# ADC.net
KiCad netlist of a schematic drawn in Altium Designer
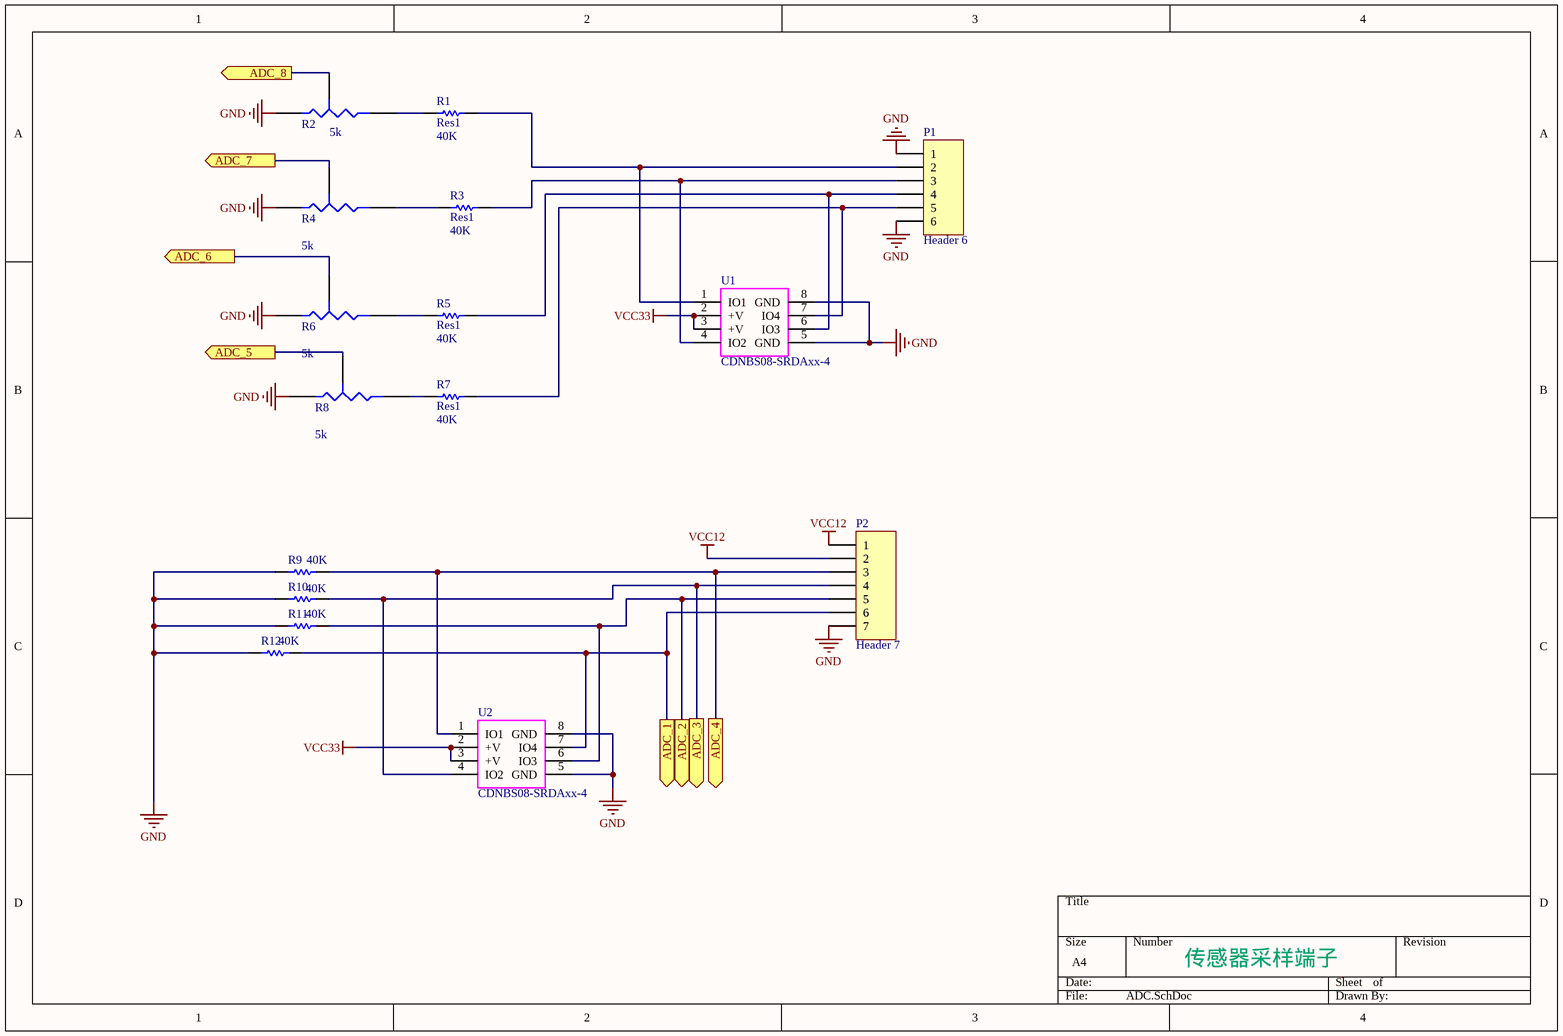
[diagram p0: ADC.SchDoc]

(export (version "E")
  (design (tool "Eeschema 10.0.6"))
  (components
    (comp (ref "P1")
      (value "Header 6")
      (footprint "3.81-6P")
      (description "Header, 6-Pin")
      (fields (field (name "PUBLISHER") "Altium Limited"))
      (libsource (lib "Miscellaneous Connectors") (part "Header 6"))
    )
    (comp (ref "P2")
      (value "Header 7")
      (footprint "3.81-7P")
      (description "Header, 7-Pin")
      (fields (field (name "PUBLISHER") "Altium Limited"))
      (libsource (lib "Miscellaneous Connectors") (part "Header 7"))
    )
    (comp (ref "R1")
      (value "Res1")
      (footprint "AXIAL-0.1")
      (description "Resistor")
      (fields (field (name "ALTIUM_VALUE") "40K") (field (name "PUBLISHER") "Altium Limited"))
      (libsource (lib "Miscellaneous Devices") (part "Res1"))
    )
    (comp (ref "R2")
      (value "5k")
      (footprint "RES-RV3296W")
      (description "Tapped Resistor")
      (fields (field (name "Comment") "Res Tap") (field (name "PUBLISHER") "Altium Limited"))
      (libsource (lib "Miscellaneous Devices") (part "Res Tap"))
    )
    (comp (ref "R3")
      (value "Res1")
      (footprint "AXIAL-0.1")
      (description "Resistor")
      (fields (field (name "ALTIUM_VALUE") "40K") (field (name "PUBLISHER") "Altium Limited"))
      (libsource (lib "Miscellaneous Devices") (part "Res1"))
    )
    (comp (ref "R4")
      (value "5k")
      (footprint "RES-RV3296W")
      (description "Tapped Resistor")
      (fields (field (name "Comment") "Res Tap") (field (name "PUBLISHER") "Altium Limited"))
      (libsource (lib "Miscellaneous Devices") (part "Res Tap"))
    )
    (comp (ref "R5")
      (value "Res1")
      (footprint "AXIAL-0.1")
      (description "Resistor")
      (fields (field (name "ALTIUM_VALUE") "40K") (field (name "PUBLISHER") "Altium Limited"))
      (libsource (lib "Miscellaneous Devices") (part "Res1"))
    )
    (comp (ref "R6")
      (value "5k")
      (footprint "RES-RV3296W")
      (description "Tapped Resistor")
      (fields (field (name "Comment") "Res Tap") (field (name "PUBLISHER") "Altium Limited"))
      (libsource (lib "Miscellaneous Devices") (part "Res Tap"))
    )
    (comp (ref "R7")
      (value "Res1")
      (footprint "AXIAL-0.1")
      (description "Resistor")
      (fields (field (name "ALTIUM_VALUE") "40K") (field (name "PUBLISHER") "Altium Limited"))
      (libsource (lib "Miscellaneous Devices") (part "Res1"))
    )
    (comp (ref "R8")
      (value "5k")
      (footprint "RES-RV3296W")
      (description "Tapped Resistor")
      (fields (field (name "Comment") "Res Tap") (field (name "PUBLISHER") "Altium Limited"))
      (libsource (lib "Miscellaneous Devices") (part "Res Tap"))
    )
    (comp (ref "R9")
      (value "40K")
      (footprint "AXIAL-0.2")
      (description "Resistor")
      (fields (field (name "Comment") "Res1") (field (name "PUBLISHER") "Altium Limited"))
      (libsource (lib "Miscellaneous Devices") (part "Res1"))
    )
    (comp (ref "R10")
      (value "40K")
      (footprint "AXIAL-0.2")
      (description "Resistor")
      (fields (field (name "Comment") "Res1") (field (name "PUBLISHER") "Altium Limited"))
      (libsource (lib "Miscellaneous Devices") (part "Res1"))
    )
    (comp (ref "R11")
      (value "40K")
      (footprint "AXIAL-0.2")
      (description "Resistor")
      (fields (field (name "Comment") "Res1") (field (name "PUBLISHER") "Altium Limited"))
      (libsource (lib "Miscellaneous Devices") (part "Res1"))
    )
    (comp (ref "R12")
      (value "40K")
      (footprint "AXIAL-0.2")
      (description "Resistor")
      (fields (field (name "Comment") "Res1") (field (name "PUBLISHER") "Altium Limited"))
      (libsource (lib "Miscellaneous Devices") (part "Res1"))
    )
    (comp (ref "U1")
      (value "CDNBS08-SRDAxx-4")
      (footprint "CDNBS08-SRDAxx-4")
      (libsource (lib "Active_crystal") (part "CDNBS08-SRDAxx-4"))
    )
    (comp (ref "U2")
      (value "CDNBS08-SRDAxx-4")
      (footprint "CDNBS08-SRDAxx-4")
      (libsource (lib "Active_crystal") (part "CDNBS08-SRDAxx-4"))
    )
  )
  (nets
    (net (code "1") (name "/ADC_1") (class "Default")
      (node (ref "P2") (pin "6") (pinfunction "6_6") (pintype "passive"))
      (node (ref "R12") (pin "2") (pinfunction "2_2") (pintype "passive"))
      (node (ref "U2") (pin "7") (pinfunction "IO4_7") (pintype "passive"))
    )
    (net (code "2") (name "/ADC_2") (class "Default")
      (node (ref "P2") (pin "5") (pinfunction "5_5") (pintype "passive"))
      (node (ref "R11") (pin "2") (pinfunction "2_2") (pintype "passive"))
      (node (ref "U2") (pin "6") (pinfunction "IO3_6") (pintype "passive"))
    )
    (net (code "3") (name "/ADC_3") (class "Default")
      (node (ref "P2") (pin "4") (pinfunction "4_4") (pintype "passive"))
      (node (ref "R10") (pin "2") (pinfunction "2_2") (pintype "passive"))
      (node (ref "U2") (pin "4") (pinfunction "IO2_4") (pintype "passive"))
    )
    (net (code "4") (name "/ADC_4") (class "Default")
      (node (ref "P2") (pin "3") (pinfunction "3_3") (pintype "passive"))
      (node (ref "R9") (pin "2") (pinfunction "2_2") (pintype "passive"))
      (node (ref "U2") (pin "1") (pinfunction "IO1_1") (pintype "passive"))
    )
    (net (code "5") (name "/ADC_5") (class "Default")
      (node (ref "R8") (pin "3") (pinfunction "TAP_3") (pintype "passive"))
    )
    (net (code "6") (name "/ADC_6") (class "Default")
      (node (ref "R6") (pin "3") (pinfunction "TAP_3") (pintype "passive"))
    )
    (net (code "7") (name "/ADC_7") (class "Default")
      (node (ref "R4") (pin "3") (pinfunction "TAP_3") (pintype "passive"))
    )
    (net (code "8") (name "/ADC_8") (class "Default")
      (node (ref "R2") (pin "3") (pinfunction "TAP_3") (pintype "passive"))
    )
    (net (code "9") (name "GND") (class "Default")
      (node (ref "P1") (pin "1") (pinfunction "1_1") (pintype "passive"))
      (node (ref "P1") (pin "6") (pinfunction "6_6") (pintype "passive"))
      (node (ref "P2") (pin "7") (pinfunction "7_7") (pintype "passive"))
      (node (ref "R10") (pin "1") (pinfunction "1_1") (pintype "passive"))
      (node (ref "R11") (pin "1") (pinfunction "1_1") (pintype "passive"))
      (node (ref "R12") (pin "1") (pinfunction "1_1") (pintype "passive"))
      (node (ref "R2") (pin "1") (pinfunction "A_1") (pintype "passive"))
      (node (ref "R4") (pin "1") (pinfunction "A_1") (pintype "passive"))
      (node (ref "R6") (pin "1") (pinfunction "A_1") (pintype "passive"))
      (node (ref "R8") (pin "1") (pinfunction "A_1") (pintype "passive"))
      (node (ref "R9") (pin "1") (pinfunction "1_1") (pintype "passive"))
      (node (ref "U1") (pin "5") (pinfunction "GND_5") (pintype "passive"))
      (node (ref "U1") (pin "8") (pinfunction "GND_8") (pintype "passive"))
      (node (ref "U2") (pin "5") (pinfunction "GND_5") (pintype "passive"))
      (node (ref "U2") (pin "8") (pinfunction "GND_8") (pintype "passive"))
    )
    (net (code "10") (name "Net-(R2-B)") (class "Default")
      (node (ref "R1") (pin "1") (pinfunction "1_1") (pintype "passive"))
      (node (ref "R2") (pin "2") (pinfunction "B_2") (pintype "passive"))
    )
    (net (code "11") (name "Net-(R4-B)") (class "Default")
      (node (ref "R3") (pin "1") (pinfunction "1_1") (pintype "passive"))
      (node (ref "R4") (pin "2") (pinfunction "B_2") (pintype "passive"))
    )
    (net (code "12") (name "Net-(R6-B)") (class "Default")
      (node (ref "R5") (pin "1") (pinfunction "1_1") (pintype "passive"))
      (node (ref "R6") (pin "2") (pinfunction "B_2") (pintype "passive"))
    )
    (net (code "13") (name "Net-(R8-B)") (class "Default")
      (node (ref "R7") (pin "1") (pinfunction "1_1") (pintype "passive"))
      (node (ref "R8") (pin "2") (pinfunction "B_2") (pintype "passive"))
    )
    (net (code "14") (name "Net-(U1-IO1)") (class "Default")
      (node (ref "P1") (pin "2") (pinfunction "2_2") (pintype "passive"))
      (node (ref "R1") (pin "2") (pinfunction "2_2") (pintype "passive"))
      (node (ref "U1") (pin "1") (pinfunction "IO1_1") (pintype "passive"))
    )
    (net (code "15") (name "Net-(U1-IO2)") (class "Default")
      (node (ref "P1") (pin "3") (pinfunction "3_3") (pintype "passive"))
      (node (ref "R3") (pin "2") (pinfunction "2_2") (pintype "passive"))
      (node (ref "U1") (pin "4") (pinfunction "IO2_4") (pintype "passive"))
    )
    (net (code "16") (name "Net-(U1-IO3)") (class "Default")
      (node (ref "P1") (pin "4") (pinfunction "4_4") (pintype "passive"))
      (node (ref "R5") (pin "2") (pinfunction "2_2") (pintype "passive"))
      (node (ref "U1") (pin "6") (pinfunction "IO3_6") (pintype "passive"))
    )
    (net (code "17") (name "Net-(U1-IO4)") (class "Default")
      (node (ref "P1") (pin "5") (pinfunction "5_5") (pintype "passive"))
      (node (ref "R7") (pin "2") (pinfunction "2_2") (pintype "passive"))
      (node (ref "U1") (pin "7") (pinfunction "IO4_7") (pintype "passive"))
    )
    (net (code "18") (name "VCC12") (class "Default")
      (node (ref "P2") (pin "1") (pinfunction "1_1") (pintype "passive"))
      (node (ref "P2") (pin "2") (pinfunction "2_2") (pintype "passive"))
    )
    (net (code "19") (name "VCC33") (class "Default")
      (node (ref "U1") (pin "2") (pinfunction "+V_2") (pintype "passive"))
      (node (ref "U1") (pin "3") (pinfunction "+V_3") (pintype "passive"))
      (node (ref "U2") (pin "2") (pinfunction "+V_2") (pintype "passive"))
      (node (ref "U2") (pin "3") (pinfunction "+V_3") (pintype "passive"))
    )
  )
)
